# Layer1_v1_0.net
KiCad netlist of a schematic drawn in EAGLE
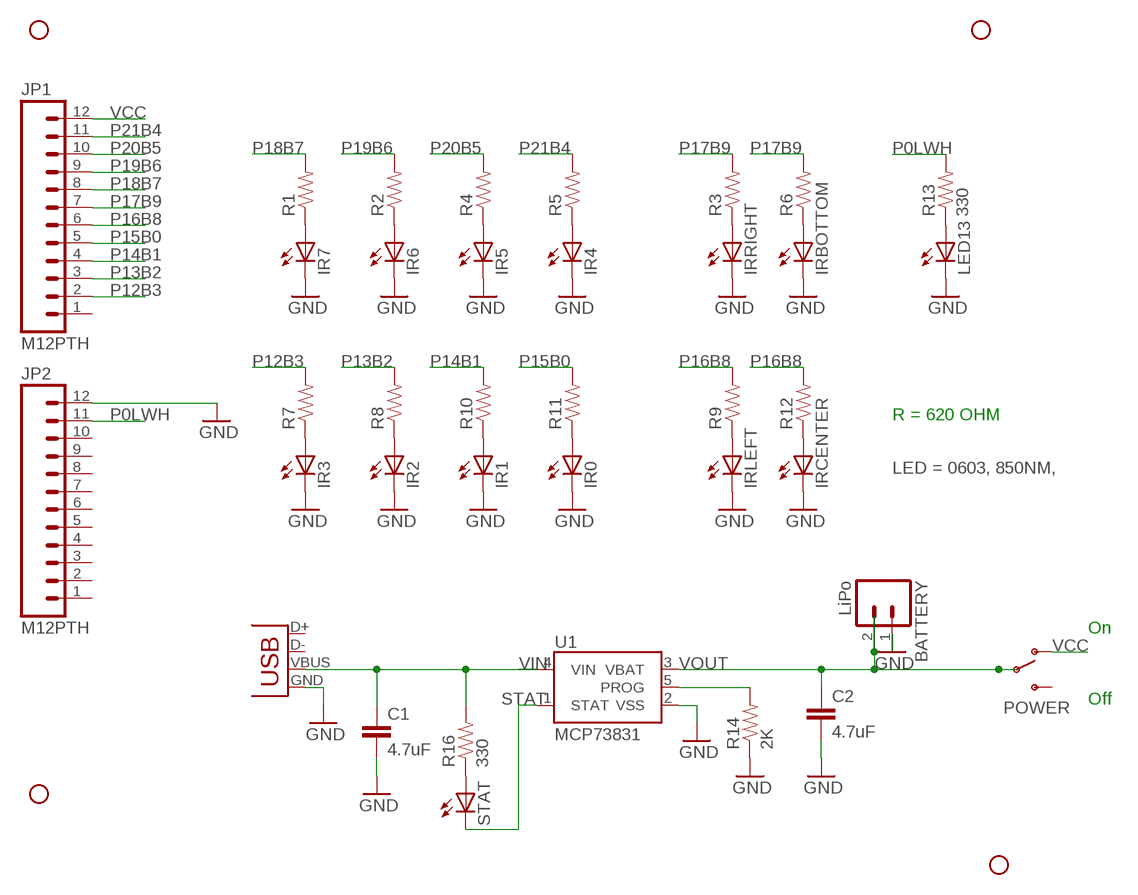
[diagram p0: schematic, sheet 1]

(export (version "E")
  (design (tool "Eeschema 10.0.6"))
  (components
    (comp (ref "BATTERY")
      (value "LiPo")
      (footprint "eagle-import:JST-2-SMD")
      (libsource (lib "eagle-import") (part "M02-JST-2MM-SMT"))
    )
    (comp (ref "C1")
      (value "4.7uF")
      (footprint "eagle-import:0603-CAP")
      (libsource (lib "eagle-import") (part "CAP0603-CAP"))
    )
    (comp (ref "C2")
      (value "4.7uF")
      (footprint "eagle-import:0603-CAP")
      (libsource (lib "eagle-import") (part "CAP0603-CAP"))
    )
    (comp (ref "IR0")
      (value "LEDCHIPLED_0603")
      (footprint "eagle-import:CHIPLED_0603")
      (libsource (lib "eagle-import") (part "LEDCHIPLED_0603"))
    )
    (comp (ref "IR1")
      (value "LEDCHIPLED_0603")
      (footprint "eagle-import:CHIPLED_0603")
      (libsource (lib "eagle-import") (part "LEDCHIPLED_0603"))
    )
    (comp (ref "IR2")
      (value "LEDCHIPLED_0603")
      (footprint "eagle-import:CHIPLED_0603")
      (libsource (lib "eagle-import") (part "LEDCHIPLED_0603"))
    )
    (comp (ref "IR3")
      (value "LEDCHIPLED_0603")
      (footprint "eagle-import:CHIPLED_0603")
      (libsource (lib "eagle-import") (part "LEDCHIPLED_0603"))
    )
    (comp (ref "IR4")
      (value "LEDCHIPLED_0603")
      (footprint "eagle-import:CHIPLED_0603")
      (libsource (lib "eagle-import") (part "LEDCHIPLED_0603"))
    )
    (comp (ref "IR5")
      (value "LEDCHIPLED_0603")
      (footprint "eagle-import:CHIPLED_0603")
      (libsource (lib "eagle-import") (part "LEDCHIPLED_0603"))
    )
    (comp (ref "IR6")
      (value "LEDCHIPLED_0603")
      (footprint "eagle-import:CHIPLED_0603")
      (libsource (lib "eagle-import") (part "LEDCHIPLED_0603"))
    )
    (comp (ref "IR7")
      (value "LEDCHIPLED_0603")
      (footprint "eagle-import:CHIPLED_0603")
      (libsource (lib "eagle-import") (part "LEDCHIPLED_0603"))
    )
    (comp (ref "IRBOTTOM")
      (value "LEDCHIPLED_0603")
      (footprint "eagle-import:CHIPLED_0603")
      (libsource (lib "eagle-import") (part "LEDCHIPLED_0603"))
    )
    (comp (ref "IRCENTER")
      (value "LEDCHIPLED_0603")
      (footprint "eagle-import:CHIPLED_0603")
      (libsource (lib "eagle-import") (part "LEDCHIPLED_0603"))
    )
    (comp (ref "IRLEFT")
      (value "LEDCHIPLED_0603")
      (footprint "eagle-import:CHIPLED_0603")
      (libsource (lib "eagle-import") (part "LEDCHIPLED_0603"))
    )
    (comp (ref "IRRIGHT")
      (value "LEDCHIPLED_0603")
      (footprint "eagle-import:CHIPLED_0603")
      (libsource (lib "eagle-import") (part "LEDCHIPLED_0603"))
    )
    (comp (ref "JP1")
      (value "M12PTH")
      (footprint "eagle-import:1X12")
      (libsource (lib "eagle-import") (part "M12PTH"))
    )
    (comp (ref "JP2")
      (value "M12PTH")
      (footprint "eagle-import:1X12")
      (libsource (lib "eagle-import") (part "M12PTH"))
    )
    (comp (ref "JP4")
      (value "STAND-OFF")
      (footprint "eagle-import:STAND-OFF")
      (libsource (lib "eagle-import") (part "STAND-OFF"))
    )
    (comp (ref "JP5")
      (value "STAND-OFF")
      (footprint "eagle-import:STAND-OFF")
      (libsource (lib "eagle-import") (part "STAND-OFF"))
    )
    (comp (ref "JP6")
      (value "STAND-OFF")
      (footprint "eagle-import:STAND-OFF")
      (libsource (lib "eagle-import") (part "STAND-OFF"))
    )
    (comp (ref "JP7")
      (value "STAND-OFF")
      (footprint "eagle-import:STAND-OFF")
      (libsource (lib "eagle-import") (part "STAND-OFF"))
    )
    (comp (ref "LED13")
      (value "LEDCHIPLED_0603")
      (footprint "eagle-import:CHIPLED_0603")
      (libsource (lib "eagle-import") (part "LEDCHIPLED_0603"))
    )
    (comp (ref "POWER")
      (value "SWITCH-SPDTPTH")
      (footprint "eagle-import:SWITCH-SPDT")
      (libsource (lib "eagle-import") (part "SWITCH-SPDTPTH"))
    )
    (comp (ref "R1")
      (value "RESISTOR0603-RES")
      (footprint "eagle-import:0603-RES")
      (libsource (lib "eagle-import") (part "RESISTOR0603-RES"))
    )
    (comp (ref "R2")
      (value "RESISTOR0603-RES")
      (footprint "eagle-import:0603-RES")
      (libsource (lib "eagle-import") (part "RESISTOR0603-RES"))
    )
    (comp (ref "R3")
      (value "RESISTOR0603-RES")
      (footprint "eagle-import:0603-RES")
      (libsource (lib "eagle-import") (part "RESISTOR0603-RES"))
    )
    (comp (ref "R4")
      (value "RESISTOR0603-RES")
      (footprint "eagle-import:0603-RES")
      (libsource (lib "eagle-import") (part "RESISTOR0603-RES"))
    )
    (comp (ref "R5")
      (value "RESISTOR0603-RES")
      (footprint "eagle-import:0603-RES")
      (libsource (lib "eagle-import") (part "RESISTOR0603-RES"))
    )
    (comp (ref "R6")
      (value "RESISTOR0603-RES")
      (footprint "eagle-import:0603-RES")
      (libsource (lib "eagle-import") (part "RESISTOR0603-RES"))
    )
    (comp (ref "R7")
      (value "RESISTOR0603-RES")
      (footprint "eagle-import:0603-RES")
      (libsource (lib "eagle-import") (part "RESISTOR0603-RES"))
    )
    (comp (ref "R8")
      (value "RESISTOR0603-RES")
      (footprint "eagle-import:0603-RES")
      (libsource (lib "eagle-import") (part "RESISTOR0603-RES"))
    )
    (comp (ref "R9")
      (value "RESISTOR0603-RES")
      (footprint "eagle-import:0603-RES")
      (libsource (lib "eagle-import") (part "RESISTOR0603-RES"))
    )
    (comp (ref "R10")
      (value "RESISTOR0603-RES")
      (footprint "eagle-import:0603-RES")
      (libsource (lib "eagle-import") (part "RESISTOR0603-RES"))
    )
    (comp (ref "R11")
      (value "RESISTOR0603-RES")
      (footprint "eagle-import:0603-RES")
      (libsource (lib "eagle-import") (part "RESISTOR0603-RES"))
    )
    (comp (ref "R12")
      (value "RESISTOR0603-RES")
      (footprint "eagle-import:0603-RES")
      (libsource (lib "eagle-import") (part "RESISTOR0603-RES"))
    )
    (comp (ref "R13")
      (value "330")
      (footprint "eagle-import:0603-RES")
      (libsource (lib "eagle-import") (part "RESISTOR0603-RES"))
    )
    (comp (ref "R14")
      (value "2K")
      (footprint "eagle-import:0603-RES")
      (libsource (lib "eagle-import") (part "RESISTOR0603-RES"))
    )
    (comp (ref "R16")
      (value "330")
      (footprint "eagle-import:0603-RES")
      (libsource (lib "eagle-import") (part "RESISTOR0603-RES"))
    )
    (comp (ref "STAT")
      (value "LEDCHIPLED_0603")
      (footprint "eagle-import:CHIPLED_0603")
      (libsource (lib "eagle-import") (part "LEDCHIPLED_0603"))
    )
    (comp (ref "U1")
      (value "MCP73831")
      (footprint "eagle-import:SOT23-5")
      (libsource (lib "eagle-import") (part "MCP73831"))
    )
    (comp (ref "X1")
      (value "USBSMD")
      (footprint "eagle-import:USB-MINIB")
      (libsource (lib "eagle-import") (part "USBSMD"))
    )
  )
  (nets
    (net (code "1") (name "/P0LWH") (class "Default")
      (node (ref "JP2") (pin "11") (pinfunction "11_11") (pintype "passive"))
      (node (ref "R13") (pin "2") (pinfunction "2_2") (pintype "passive"))
    )
    (net (code "2") (name "/P12B3") (class "Default")
      (node (ref "JP1") (pin "2") (pinfunction "2_2") (pintype "passive"))
      (node (ref "R7") (pin "2") (pinfunction "2_2") (pintype "passive"))
    )
    (net (code "3") (name "/P13B2") (class "Default")
      (node (ref "JP1") (pin "3") (pinfunction "3_3") (pintype "passive"))
      (node (ref "R8") (pin "2") (pinfunction "2_2") (pintype "passive"))
    )
    (net (code "4") (name "/P14B1") (class "Default")
      (node (ref "JP1") (pin "4") (pinfunction "4_4") (pintype "passive"))
      (node (ref "R10") (pin "2") (pinfunction "2_2") (pintype "passive"))
    )
    (net (code "5") (name "/P15B0") (class "Default")
      (node (ref "JP1") (pin "5") (pinfunction "5_5") (pintype "passive"))
      (node (ref "R11") (pin "2") (pinfunction "2_2") (pintype "passive"))
    )
    (net (code "6") (name "/P16B8") (class "Default")
      (node (ref "JP1") (pin "6") (pinfunction "6_6") (pintype "passive"))
      (node (ref "R12") (pin "2") (pinfunction "2_2") (pintype "passive"))
      (node (ref "R9") (pin "2") (pinfunction "2_2") (pintype "passive"))
    )
    (net (code "7") (name "/P17B9") (class "Default")
      (node (ref "JP1") (pin "7") (pinfunction "7_7") (pintype "passive"))
      (node (ref "R3") (pin "2") (pinfunction "2_2") (pintype "passive"))
      (node (ref "R6") (pin "2") (pinfunction "2_2") (pintype "passive"))
    )
    (net (code "8") (name "/P18B7") (class "Default")
      (node (ref "JP1") (pin "8") (pinfunction "8_8") (pintype "passive"))
      (node (ref "R1") (pin "2") (pinfunction "2_2") (pintype "passive"))
    )
    (net (code "9") (name "/P19B6") (class "Default")
      (node (ref "JP1") (pin "9") (pinfunction "9_9") (pintype "passive"))
      (node (ref "R2") (pin "2") (pinfunction "2_2") (pintype "passive"))
    )
    (net (code "10") (name "/P20B5") (class "Default")
      (node (ref "JP1") (pin "10") (pinfunction "10_10") (pintype "passive"))
      (node (ref "R4") (pin "2") (pinfunction "2_2") (pintype "passive"))
    )
    (net (code "11") (name "/P21B4") (class "Default")
      (node (ref "JP1") (pin "11") (pinfunction "11_11") (pintype "passive"))
      (node (ref "R5") (pin "2") (pinfunction "2_2") (pintype "passive"))
    )
    (net (code "12") (name "/STAT") (class "Default")
      (node (ref "STAT") (pin "C") (pinfunction "C_C") (pintype "passive"))
      (node (ref "U1") (pin "1") (pinfunction "STAT_1") (pintype "output"))
    )
    (net (code "13") (name "/VCC") (class "Default")
      (node (ref "JP1") (pin "12") (pinfunction "12_12") (pintype "passive"))
      (node (ref "POWER") (pin "1") (pinfunction "O_1") (pintype "passive"))
    )
    (net (code "14") (name "/VIN") (class "Default")
      (node (ref "C1") (pin "1") (pinfunction "1_1") (pintype "passive"))
      (node (ref "R16") (pin "2") (pinfunction "2_2") (pintype "passive"))
      (node (ref "U1") (pin "4") (pinfunction "VIN_4") (pintype "power_in"))
      (node (ref "X1") (pin "VBUS") (pinfunction "VBUS_VBUS") (pintype "bidirectional"))
    )
    (net (code "15") (name "/VOUT") (class "Default")
      (node (ref "BATTERY") (pin "2") (pinfunction "1_2") (pintype "passive"))
      (node (ref "C2") (pin "1") (pinfunction "1_1") (pintype "passive"))
      (node (ref "POWER") (pin "2") (pinfunction "P_2") (pintype "passive"))
      (node (ref "U1") (pin "3") (pinfunction "VBAT_3") (pintype "power_in"))
    )
    (net (code "16") (name "GND") (class "Default")
      (node (ref "BATTERY") (pin "1") (pinfunction "2_1") (pintype "passive"))
      (node (ref "C1") (pin "2") (pinfunction "2_2") (pintype "passive"))
      (node (ref "C2") (pin "2") (pinfunction "2_2") (pintype "passive"))
      (node (ref "IR0") (pin "C") (pinfunction "C_C") (pintype "passive"))
      (node (ref "IR1") (pin "C") (pinfunction "C_C") (pintype "passive"))
      (node (ref "IR2") (pin "C") (pinfunction "C_C") (pintype "passive"))
      (node (ref "IR3") (pin "C") (pinfunction "C_C") (pintype "passive"))
      (node (ref "IR4") (pin "C") (pinfunction "C_C") (pintype "passive"))
      (node (ref "IR5") (pin "C") (pinfunction "C_C") (pintype "passive"))
      (node (ref "IR6") (pin "C") (pinfunction "C_C") (pintype "passive"))
      (node (ref "IR7") (pin "C") (pinfunction "C_C") (pintype "passive"))
      (node (ref "IRBOTTOM") (pin "C") (pinfunction "C_C") (pintype "passive"))
      (node (ref "IRCENTER") (pin "C") (pinfunction "C_C") (pintype "passive"))
      (node (ref "IRLEFT") (pin "C") (pinfunction "C_C") (pintype "passive"))
      (node (ref "IRRIGHT") (pin "C") (pinfunction "C_C") (pintype "passive"))
      (node (ref "JP2") (pin "12") (pinfunction "12_12") (pintype "passive"))
      (node (ref "LED13") (pin "C") (pinfunction "C_C") (pintype "passive"))
      (node (ref "R14") (pin "1") (pinfunction "1_1") (pintype "passive"))
      (node (ref "U1") (pin "2") (pinfunction "VSS_2") (pintype "power_in"))
      (node (ref "X1") (pin "GND") (pinfunction "GND_GND") (pintype "bidirectional"))
    )
    (net (code "17") (name "Net-(IR0-PadA)") (class "Default")
      (node (ref "IR0") (pin "A") (pinfunction "A_A") (pintype "passive"))
      (node (ref "R11") (pin "1") (pinfunction "1_1") (pintype "passive"))
    )
    (net (code "18") (name "Net-(IR1-PadA)") (class "Default")
      (node (ref "IR1") (pin "A") (pinfunction "A_A") (pintype "passive"))
      (node (ref "R10") (pin "1") (pinfunction "1_1") (pintype "passive"))
    )
    (net (code "19") (name "Net-(IR2-PadA)") (class "Default")
      (node (ref "IR2") (pin "A") (pinfunction "A_A") (pintype "passive"))
      (node (ref "R8") (pin "1") (pinfunction "1_1") (pintype "passive"))
    )
    (net (code "20") (name "Net-(IR3-PadA)") (class "Default")
      (node (ref "IR3") (pin "A") (pinfunction "A_A") (pintype "passive"))
      (node (ref "R7") (pin "1") (pinfunction "1_1") (pintype "passive"))
    )
    (net (code "21") (name "Net-(IR4-PadA)") (class "Default")
      (node (ref "IR4") (pin "A") (pinfunction "A_A") (pintype "passive"))
      (node (ref "R5") (pin "1") (pinfunction "1_1") (pintype "passive"))
    )
    (net (code "22") (name "Net-(IR5-PadA)") (class "Default")
      (node (ref "IR5") (pin "A") (pinfunction "A_A") (pintype "passive"))
      (node (ref "R4") (pin "1") (pinfunction "1_1") (pintype "passive"))
    )
    (net (code "23") (name "Net-(IR6-PadA)") (class "Default")
      (node (ref "IR6") (pin "A") (pinfunction "A_A") (pintype "passive"))
      (node (ref "R2") (pin "1") (pinfunction "1_1") (pintype "passive"))
    )
    (net (code "24") (name "Net-(IR7-PadA)") (class "Default")
      (node (ref "IR7") (pin "A") (pinfunction "A_A") (pintype "passive"))
      (node (ref "R1") (pin "1") (pinfunction "1_1") (pintype "passive"))
    )
    (net (code "25") (name "Net-(IRBOTTOM-PadA)") (class "Default")
      (node (ref "IRBOTTOM") (pin "A") (pinfunction "A_A") (pintype "passive"))
      (node (ref "R6") (pin "1") (pinfunction "1_1") (pintype "passive"))
    )
    (net (code "26") (name "Net-(IRCENTER-PadA)") (class "Default")
      (node (ref "IRCENTER") (pin "A") (pinfunction "A_A") (pintype "passive"))
      (node (ref "R12") (pin "1") (pinfunction "1_1") (pintype "passive"))
    )
    (net (code "27") (name "Net-(IRLEFT-PadA)") (class "Default")
      (node (ref "IRLEFT") (pin "A") (pinfunction "A_A") (pintype "passive"))
      (node (ref "R9") (pin "1") (pinfunction "1_1") (pintype "passive"))
    )
    (net (code "28") (name "Net-(IRRIGHT-PadA)") (class "Default")
      (node (ref "IRRIGHT") (pin "A") (pinfunction "A_A") (pintype "passive"))
      (node (ref "R3") (pin "1") (pinfunction "1_1") (pintype "passive"))
    )
    (net (code "29") (name "Net-(LED13-PadA)") (class "Default")
      (node (ref "LED13") (pin "A") (pinfunction "A_A") (pintype "passive"))
      (node (ref "R13") (pin "1") (pinfunction "1_1") (pintype "passive"))
    )
    (net (code "30") (name "Net-(R16-Pad1)") (class "Default")
      (node (ref "R16") (pin "1") (pinfunction "1_1") (pintype "passive"))
      (node (ref "STAT") (pin "A") (pinfunction "A_A") (pintype "passive"))
    )
    (net (code "31") (name "Net-(U1-PROG)") (class "Default")
      (node (ref "R14") (pin "2") (pinfunction "2_2") (pintype "passive"))
      (node (ref "U1") (pin "5") (pinfunction "PROG_5") (pintype "input"))
    )
    (net (code "32") (name "unconnected-(JP1-Pad1)") (class "Default")
      (node (ref "JP1") (pin "1") (pinfunction "1_1") (pintype "passive"))
    )
    (net (code "33") (name "unconnected-(JP2-Pad1)") (class "Default")
      (node (ref "JP2") (pin "1") (pinfunction "1_1") (pintype "passive"))
    )
    (net (code "34") (name "unconnected-(JP2-Pad2)") (class "Default")
      (node (ref "JP2") (pin "2") (pinfunction "2_2") (pintype "passive"))
    )
    (net (code "35") (name "unconnected-(JP2-Pad3)") (class "Default")
      (node (ref "JP2") (pin "3") (pinfunction "3_3") (pintype "passive"))
    )
    (net (code "36") (name "unconnected-(JP2-Pad4)") (class "Default")
      (node (ref "JP2") (pin "4") (pinfunction "4_4") (pintype "passive"))
    )
    (net (code "37") (name "unconnected-(JP2-Pad5)") (class "Default")
      (node (ref "JP2") (pin "5") (pinfunction "5_5") (pintype "passive"))
    )
    (net (code "38") (name "unconnected-(JP2-Pad6)") (class "Default")
      (node (ref "JP2") (pin "6") (pinfunction "6_6") (pintype "passive"))
    )
    (net (code "39") (name "unconnected-(JP2-Pad7)") (class "Default")
      (node (ref "JP2") (pin "7") (pinfunction "7_7") (pintype "passive"))
    )
    (net (code "40") (name "unconnected-(JP2-Pad8)") (class "Default")
      (node (ref "JP2") (pin "8") (pinfunction "8_8") (pintype "passive"))
    )
    (net (code "41") (name "unconnected-(JP2-Pad9)") (class "Default")
      (node (ref "JP2") (pin "9") (pinfunction "9_9") (pintype "passive"))
    )
    (net (code "42") (name "unconnected-(JP2-Pad10)") (class "Default")
      (node (ref "JP2") (pin "10") (pinfunction "10_10") (pintype "passive"))
    )
    (net (code "43") (name "unconnected-(POWER-S-Pad3)") (class "Default")
      (node (ref "POWER") (pin "3") (pinfunction "S_3") (pintype "passive"))
    )
    (net (code "44") (name "unconnected-(X1-PadD+)") (class "Default")
      (node (ref "X1") (pin "D+") (pinfunction "D+_D+") (pintype "bidirectional"))
    )
    (net (code "45") (name "unconnected-(X1-PadD-)") (class "Default")
      (node (ref "X1") (pin "D-") (pinfunction "D-_D-") (pintype "bidirectional"))
    )
  )
)
